# ACVoltage.net
KiCad netlist of a schematic drawn in EAGLE
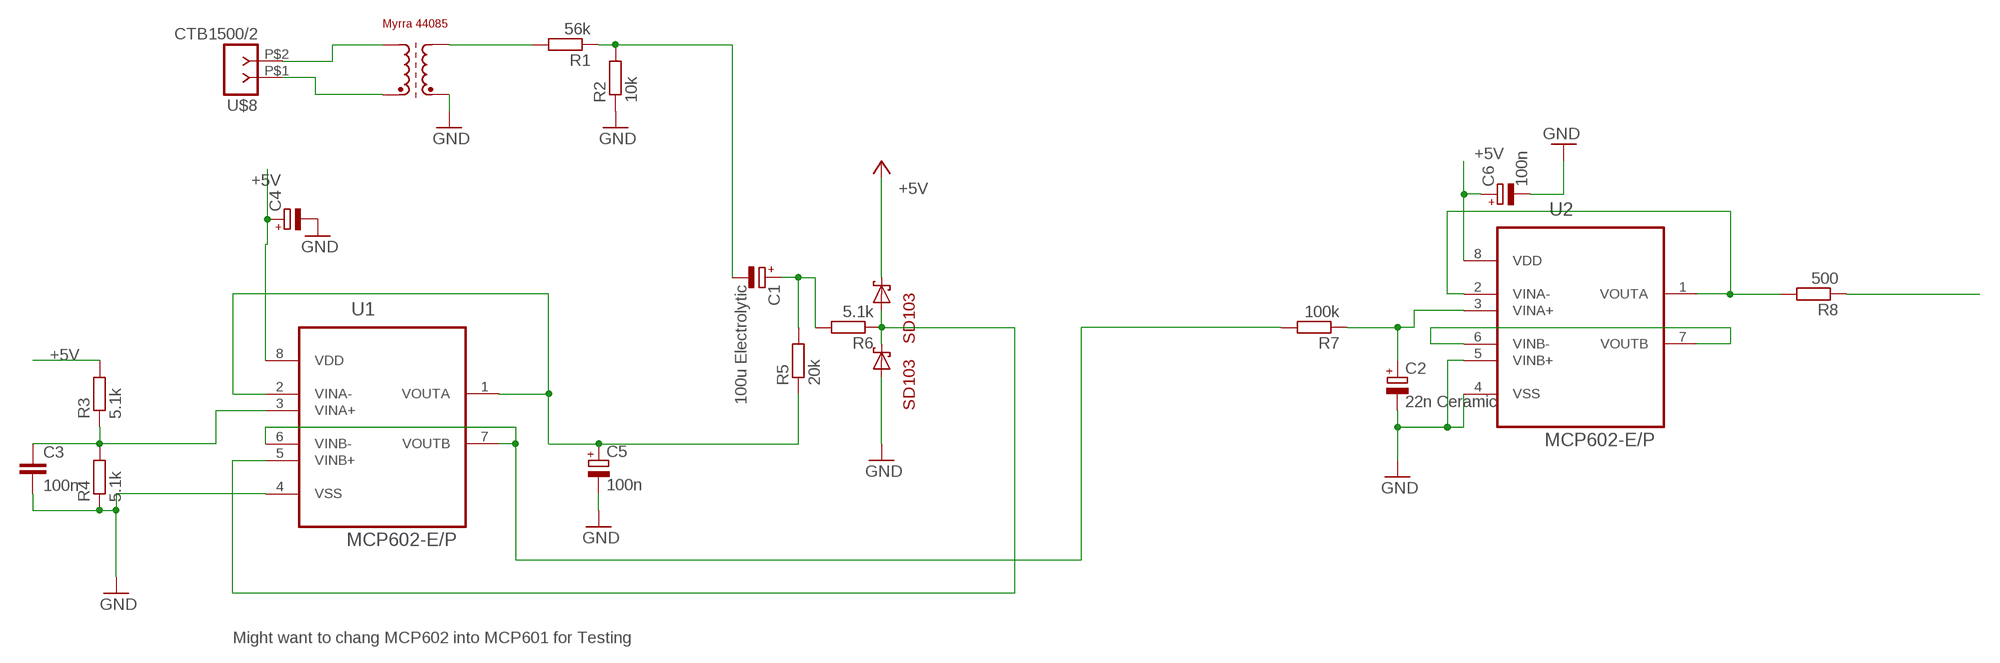
[diagram p0: schematic, sheet 1]

(export (version "E")
  (design (tool "Eeschema 10.0.6"))
  (components
    (comp (ref "C1")
      (value "100u Electrolytic")
      (footprint "eagle-import:E2,5-7---100UF")
      (libsource (lib "eagle-import") (part "CPOL1"))
    )
    (comp (ref "C2")
      (value "22n Ceramic")
      (footprint "eagle-import:E2,5-7---100UF")
      (libsource (lib "eagle-import") (part "CPOL1"))
    )
    (comp (ref "C3")
      (value "100n")
      (footprint "eagle-import:C050-030-075")
      (libsource (lib "eagle-import") (part "C5P"))
    )
    (comp (ref "C4")
      (value "CPOL1")
      (footprint "eagle-import:E2,5-7---100UF")
      (libsource (lib "eagle-import") (part "CPOL1"))
    )
    (comp (ref "C5")
      (value "100n")
      (footprint "eagle-import:E2,5-7---100UF")
      (libsource (lib "eagle-import") (part "CPOL1"))
    )
    (comp (ref "C6")
      (value "100n")
      (footprint "eagle-import:E2,5-7---100UF")
      (libsource (lib "eagle-import") (part "CPOL1"))
    )
    (comp (ref "R1")
      (value "56k")
      (footprint "eagle-import:0207_10")
      (libsource (lib "eagle-import") (part "R"))
    )
    (comp (ref "R2")
      (value "10k")
      (footprint "eagle-import:0207_10")
      (libsource (lib "eagle-import") (part "R"))
    )
    (comp (ref "R3")
      (value "5.1k")
      (footprint "eagle-import:0207_10")
      (libsource (lib "eagle-import") (part "R"))
    )
    (comp (ref "R4")
      (value "5.1k")
      (footprint "eagle-import:0207_10")
      (libsource (lib "eagle-import") (part "R"))
    )
    (comp (ref "R5")
      (value "20k")
      (footprint "eagle-import:0207_10")
      (libsource (lib "eagle-import") (part "R"))
    )
    (comp (ref "R6")
      (value "5.1k")
      (footprint "eagle-import:0207_10")
      (libsource (lib "eagle-import") (part "R"))
    )
    (comp (ref "R7")
      (value "100k")
      (footprint "eagle-import:0207_10")
      (libsource (lib "eagle-import") (part "R"))
    )
    (comp (ref "R8")
      (value "500")
      (footprint "eagle-import:0207_10")
      (libsource (lib "eagle-import") (part "R"))
    )
    (comp (ref "U$5")
      (value "MYRRA_4408")
      (footprint "eagle-import:4408")
      (libsource (lib "eagle-import") (part "MYRRA_4408"))
    )
    (comp (ref "U$6")
      (value "SD103A")
      (footprint "eagle-import:D035-10")
      (libsource (lib "eagle-import") (part "SD103A"))
    )
    (comp (ref "U$7")
      (value "SD103A")
      (footprint "eagle-import:D035-10")
      (libsource (lib "eagle-import") (part "SD103A"))
    )
    (comp (ref "U$8")
      (value "CTB1500/2")
      (footprint "eagle-import:CTB1500-2")
      (libsource (lib "eagle-import") (part "CTB1500/2"))
    )
    (comp (ref "U1")
      (value "MCP602-E/P")
      (footprint "eagle-import:DIP254P762X508-8P")
      (libsource (lib "eagle-import") (part "MCP602-E/P"))
    )
    (comp (ref "U2")
      (value "MCP602-E/P")
      (footprint "eagle-import:DIP254P762X508-8P")
      (libsource (lib "eagle-import") (part "MCP602-E/P"))
    )
  )
  (nets
    (net (code "1") (name "+3V3") (class "Default")
      (node (ref "C4") (pin "+") (pinfunction "+_+") (pintype "passive"))
      (node (ref "C6") (pin "+") (pinfunction "+_+") (pintype "passive"))
      (node (ref "R3") (pin "2") (pinfunction "2_2") (pintype "passive"))
      (node (ref "U$6") (pin "C") (pinfunction "C_C") (pintype "passive"))
      (node (ref "U1") (pin "8") (pinfunction "VDD_8") (pintype "power_in"))
      (node (ref "U2") (pin "8") (pinfunction "VDD_8") (pintype "power_in"))
    )
    (net (code "2") (name "GND") (class "Default")
      (node (ref "C2") (pin "-") (pinfunction "-_-") (pintype "passive"))
      (node (ref "C3") (pin "2") (pinfunction "2_2") (pintype "passive"))
      (node (ref "C4") (pin "-") (pinfunction "-_-") (pintype "passive"))
      (node (ref "C5") (pin "-") (pinfunction "-_-") (pintype "passive"))
      (node (ref "C6") (pin "-") (pinfunction "-_-") (pintype "passive"))
      (node (ref "R2") (pin "1") (pinfunction "1_1") (pintype "passive"))
      (node (ref "R4") (pin "1") (pinfunction "1_1") (pintype "passive"))
      (node (ref "U$5") (pin "PIN9") (pinfunction "E2_PIN9") (pintype "passive"))
      (node (ref "U$7") (pin "A") (pinfunction "A_A") (pintype "passive"))
      (node (ref "U1") (pin "4") (pinfunction "VSS_4") (pintype "power_in"))
      (node (ref "U2") (pin "4") (pinfunction "VSS_4") (pintype "power_in"))
      (node (ref "U2") (pin "5") (pinfunction "VINB+_5") (pintype "input"))
    )
    (net (code "3") (name "Net-(C1-Pad+)") (class "Default")
      (node (ref "C1") (pin "+") (pinfunction "+_+") (pintype "passive"))
      (node (ref "R5") (pin "2") (pinfunction "2_2") (pintype "passive"))
      (node (ref "R6") (pin "2") (pinfunction "2_2") (pintype "passive"))
    )
    (net (code "4") (name "Net-(C1-Pad-)") (class "Default")
      (node (ref "C1") (pin "-") (pinfunction "-_-") (pintype "passive"))
      (node (ref "R1") (pin "1") (pinfunction "1_1") (pintype "passive"))
      (node (ref "R2") (pin "2") (pinfunction "2_2") (pintype "passive"))
    )
    (net (code "5") (name "Net-(U$5-A1)") (class "Default")
      (node (ref "U$5") (pin "PIN5") (pinfunction "A1_PIN5") (pintype "passive"))
      (node (ref "U$8") (pin "P$2") (pinfunction "2_P$2") (pintype "passive"))
    )
    (net (code "6") (name "Net-(U$5-A2)") (class "Default")
      (node (ref "R1") (pin "2") (pinfunction "2_2") (pintype "passive"))
      (node (ref "U$5") (pin "PIN7") (pinfunction "A2_PIN7") (pintype "passive"))
    )
    (net (code "7") (name "Net-(U$5-E1)") (class "Default")
      (node (ref "U$5") (pin "PIN1") (pinfunction "E1_PIN1") (pintype "passive"))
      (node (ref "U$8") (pin "P$1") (pinfunction "1_P$1") (pintype "passive"))
    )
    (net (code "8") (name "Net-(U1-VINA+)") (class "Default")
      (node (ref "C3") (pin "1") (pinfunction "1_1") (pintype "passive"))
      (node (ref "R3") (pin "1") (pinfunction "1_1") (pintype "passive"))
      (node (ref "R4") (pin "2") (pinfunction "2_2") (pintype "passive"))
      (node (ref "U1") (pin "3") (pinfunction "VINA+_3") (pintype "input"))
    )
    (net (code "9") (name "Net-(U1-VINA-)") (class "Default")
      (node (ref "C5") (pin "+") (pinfunction "+_+") (pintype "passive"))
      (node (ref "R5") (pin "1") (pinfunction "1_1") (pintype "passive"))
      (node (ref "U1") (pin "1") (pinfunction "VOUTA_1") (pintype "output"))
      (node (ref "U1") (pin "2") (pinfunction "VINA-_2") (pintype "input"))
    )
    (net (code "10") (name "Net-(U1-VINB+)") (class "Default")
      (node (ref "R6") (pin "1") (pinfunction "1_1") (pintype "passive"))
      (node (ref "U$6") (pin "A") (pinfunction "A_A") (pintype "passive"))
      (node (ref "U$7") (pin "C") (pinfunction "C_C") (pintype "passive"))
      (node (ref "U1") (pin "5") (pinfunction "VINB+_5") (pintype "input"))
    )
    (net (code "11") (name "Net-(U1-VINB-)") (class "Default")
      (node (ref "R7") (pin "2") (pinfunction "2_2") (pintype "passive"))
      (node (ref "U1") (pin "6") (pinfunction "VINB-_6") (pintype "input"))
      (node (ref "U1") (pin "7") (pinfunction "VOUTB_7") (pintype "output"))
    )
    (net (code "12") (name "Net-(U2-VINA+)") (class "Default")
      (node (ref "C2") (pin "+") (pinfunction "+_+") (pintype "passive"))
      (node (ref "R7") (pin "1") (pinfunction "1_1") (pintype "passive"))
      (node (ref "U2") (pin "3") (pinfunction "VINA+_3") (pintype "input"))
    )
    (net (code "13") (name "Net-(U2-VINA-)") (class "Default")
      (node (ref "R8") (pin "2") (pinfunction "2_2") (pintype "passive"))
      (node (ref "U2") (pin "1") (pinfunction "VOUTA_1") (pintype "output"))
      (node (ref "U2") (pin "2") (pinfunction "VINA-_2") (pintype "input"))
    )
    (net (code "14") (name "Net-(U2-VINB-)") (class "Default")
      (node (ref "U2") (pin "6") (pinfunction "VINB-_6") (pintype "input"))
      (node (ref "U2") (pin "7") (pinfunction "VOUTB_7") (pintype "output"))
    )
    (net (code "15") (name "unconnected-(R8-Pad1)") (class "Default")
      (node (ref "R8") (pin "1") (pinfunction "1_1") (pintype "passive"))
    )
  )
)
